# MCU_Module_V3.net
KiCad netlist of a schematic drawn in EAGLE
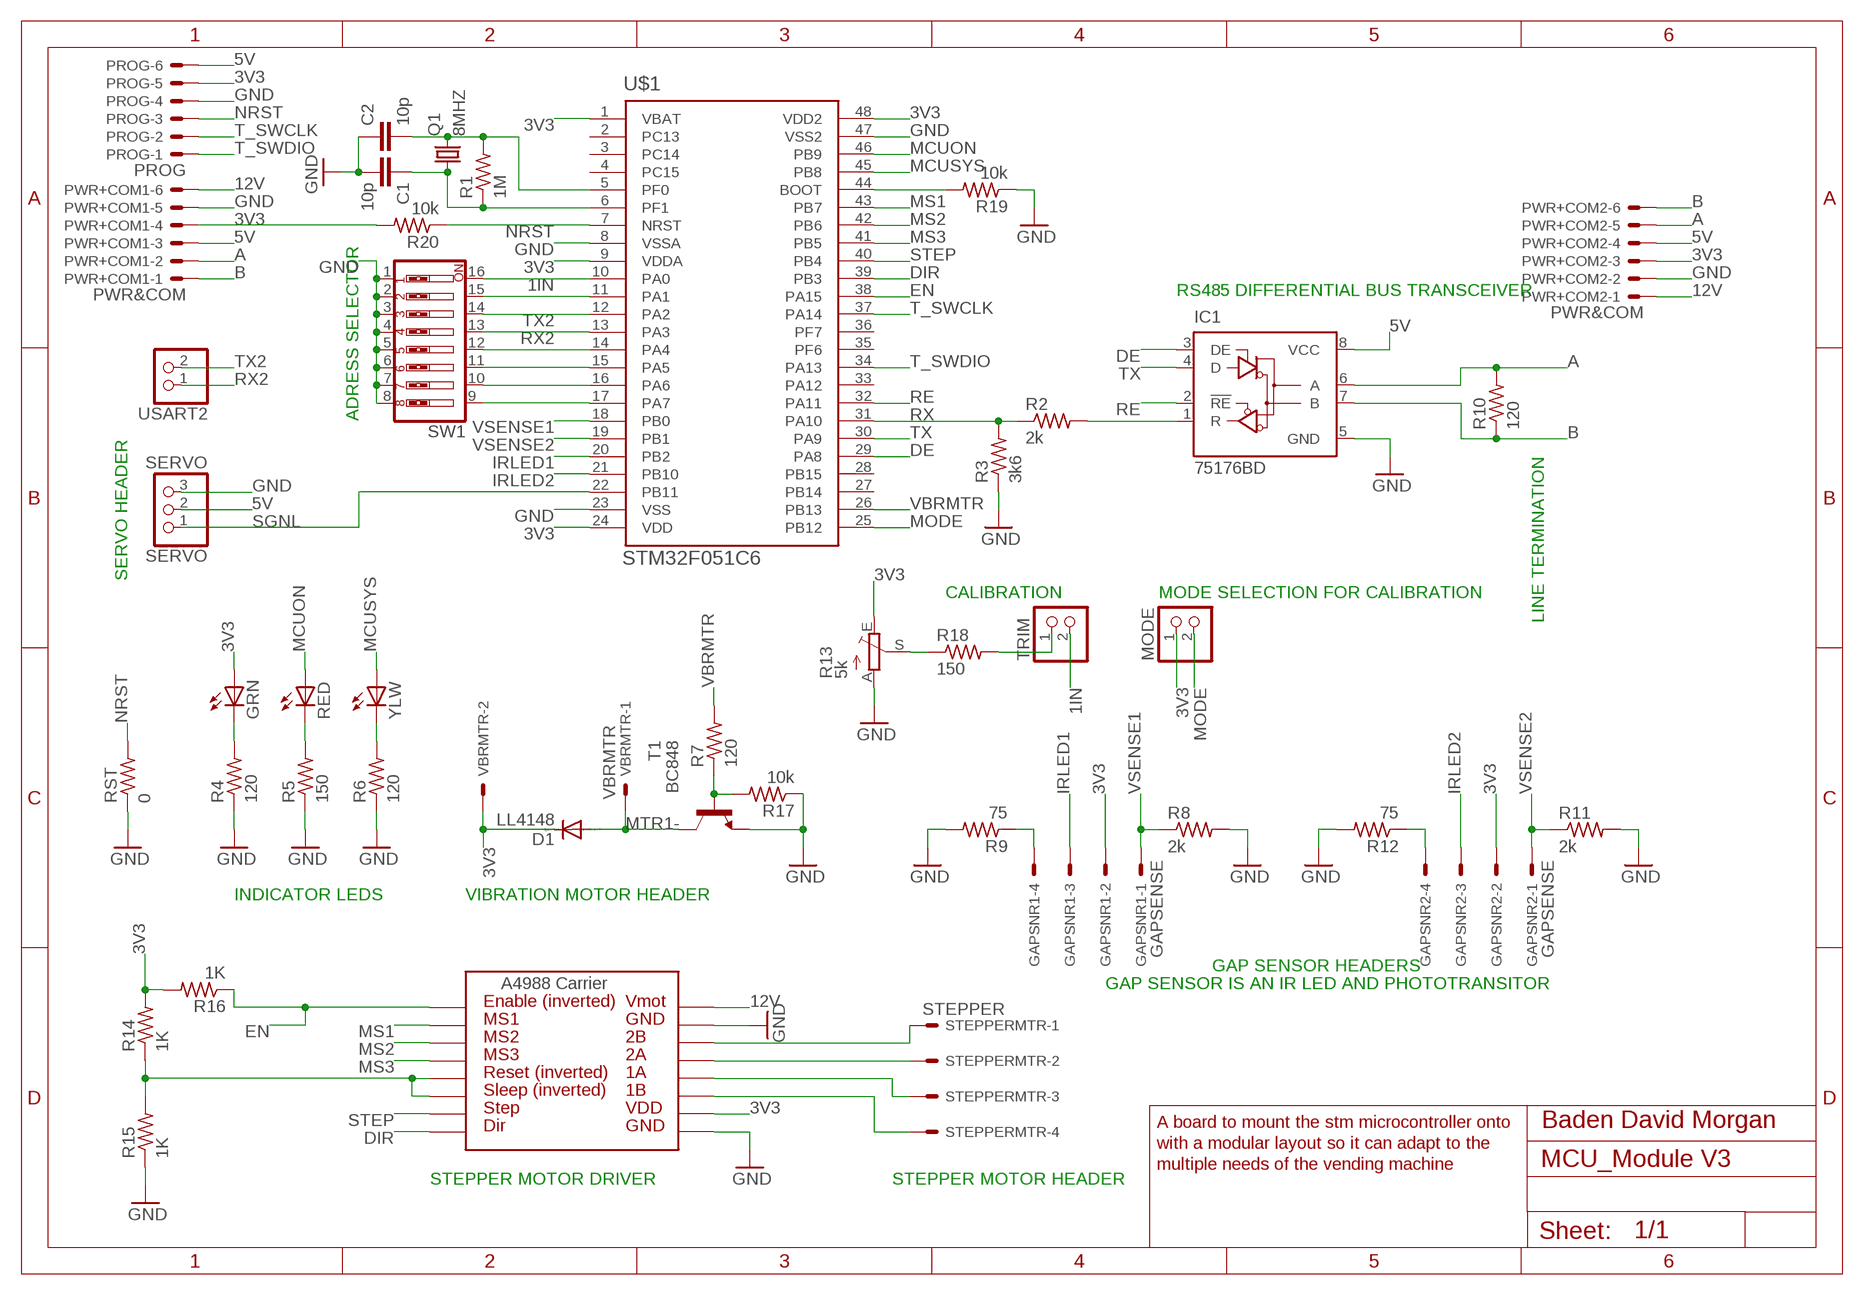
[diagram p0: schematic, sheet 1]

(export (version "E")
  (design (tool "Eeschema 10.0.6"))
  (components
    (comp (ref "C1")
      (value "10p")
      (footprint "eagle-import:C0805")
      (libsource (lib "eagle-import") (part "C-EUC0805"))
    )
    (comp (ref "C2")
      (value "10p")
      (footprint "eagle-import:C0805")
      (libsource (lib "eagle-import") (part "C-EUC0805"))
    )
    (comp (ref "D1")
      (value "LL4148")
      (footprint "eagle-import:SOD80C")
      (libsource (lib "eagle-import") (part "PMLL4150"))
    )
    (comp (ref "GAPSNR1")
      (value "GAPSENSE")
      (footprint "eagle-import:6410-04")
      (libsource (lib "eagle-import") (part "22-?-0427-2041"))
    )
    (comp (ref "GAPSNR2")
      (value "GAPSENSE")
      (footprint "eagle-import:6410-04")
      (libsource (lib "eagle-import") (part "22-?-0427-2041"))
    )
    (comp (ref "GRN")
      (value "LEDSML1206")
      (footprint "eagle-import:SML1206")
      (libsource (lib "eagle-import") (part "LEDSML1206"))
    )
    (comp (ref "IC1")
      (value "75176BD")
      (footprint "eagle-import:D_R-PDSO-G8")
      (libsource (lib "eagle-import") (part "75176AD"))
    )
    (comp (ref "MODE")
      (value "PINHD-1X2")
      (footprint "eagle-import:1X02")
      (libsource (lib "eagle-import") (part "PINHD-1X2"))
    )
    (comp (ref "PROG")
      (value "PROG")
      (footprint "eagle-import:6410-06")
      (libsource (lib "eagle-import") (part "22-?-0627-2061"))
    )
    (comp (ref "PWR+COM1")
      (value "PWR&COM")
      (footprint "eagle-import:7395-06")
      (libsource (lib "eagle-import") (part "22-?-0605-7068"))
    )
    (comp (ref "PWR+COM2")
      (value "PWR&COM")
      (footprint "eagle-import:7395-06")
      (libsource (lib "eagle-import") (part "22-?-0605-7068"))
    )
    (comp (ref "Q1")
      (value "8MHZ")
      (footprint "eagle-import:SM49")
      (libsource (lib "eagle-import") (part "CRYSTALSM49"))
    )
    (comp (ref "R1")
      (value "1M")
      (footprint "eagle-import:R0805")
      (libsource (lib "eagle-import") (part "R-US_R0805"))
    )
    (comp (ref "R2")
      (value "2k")
      (footprint "eagle-import:R0805")
      (libsource (lib "eagle-import") (part "resistor_R-US_R0805"))
    )
    (comp (ref "R3")
      (value "3k6")
      (footprint "eagle-import:R0805")
      (libsource (lib "eagle-import") (part "resistor_R-US_R0805"))
    )
    (comp (ref "R4")
      (value "120")
      (footprint "eagle-import:R0805")
      (libsource (lib "eagle-import") (part "R-US_R0805"))
    )
    (comp (ref "R5")
      (value "150")
      (footprint "eagle-import:R0805")
      (libsource (lib "eagle-import") (part "R-US_R0805"))
    )
    (comp (ref "R6")
      (value "120")
      (footprint "eagle-import:R0805")
      (libsource (lib "eagle-import") (part "R-US_R0805"))
    )
    (comp (ref "R7")
      (value "120")
      (footprint "eagle-import:R0805")
      (libsource (lib "eagle-import") (part "R-US_R0805"))
    )
    (comp (ref "R8")
      (value "2k")
      (footprint "eagle-import:R0805")
      (libsource (lib "eagle-import") (part "resistor_R-US_R0805"))
    )
    (comp (ref "R9")
      (value "75")
      (footprint "eagle-import:R0805")
      (libsource (lib "eagle-import") (part "R-US_R0805"))
    )
    (comp (ref "R10")
      (value "120")
      (footprint "eagle-import:R0805")
      (libsource (lib "eagle-import") (part "resistor_R-US_R0805"))
    )
    (comp (ref "R11")
      (value "2k")
      (footprint "eagle-import:R0805")
      (libsource (lib "eagle-import") (part "resistor_R-US_R0805"))
    )
    (comp (ref "R12")
      (value "75")
      (footprint "eagle-import:R0805")
      (libsource (lib "eagle-import") (part "R-US_R0805"))
    )
    (comp (ref "R13")
      (value "5k")
      (footprint "eagle-import:B25P")
      (libsource (lib "eagle-import") (part "TRIM_EU-B25P"))
    )
    (comp (ref "R14")
      (value "1K")
      (footprint "eagle-import:R0805")
      (libsource (lib "eagle-import") (part "R-US_R0805"))
    )
    (comp (ref "R15")
      (value "1K")
      (footprint "eagle-import:R0805")
      (libsource (lib "eagle-import") (part "R-US_R0805"))
    )
    (comp (ref "R16")
      (value "1K")
      (footprint "eagle-import:R0805")
      (libsource (lib "eagle-import") (part "R-US_R0805"))
    )
    (comp (ref "R17")
      (value "10k")
      (footprint "eagle-import:R0805")
      (libsource (lib "eagle-import") (part "R-US_R0805"))
    )
    (comp (ref "R18")
      (value "150")
      (footprint "eagle-import:R0805")
      (libsource (lib "eagle-import") (part "resistor_R-US_R0805"))
    )
    (comp (ref "R19")
      (value "10k")
      (footprint "eagle-import:R0805")
      (libsource (lib "eagle-import") (part "R-US_R0805"))
    )
    (comp (ref "R20")
      (value "10k")
      (footprint "eagle-import:R0805")
      (libsource (lib "eagle-import") (part "R-US_R0805"))
    )
    (comp (ref "RED")
      (value "LEDSML1206")
      (footprint "eagle-import:SML1206")
      (libsource (lib "eagle-import") (part "LEDSML1206"))
    )
    (comp (ref "RST")
      (value "0")
      (footprint "eagle-import:R0805")
      (libsource (lib "eagle-import") (part "R-US_R0805"))
    )
    (comp (ref "SERVO")
      (value "SERVO")
      (footprint "eagle-import:1X03")
      (libsource (lib "eagle-import") (part "PINHD-1X3"))
    )
    (comp (ref "STEPPERMTR")
      (value "STEPPER")
      (footprint "eagle-import:6410-04")
      (libsource (lib "eagle-import") (part "22-?-0427-2041"))
    )
    (comp (ref "SW1")
      (value "SW_DIP-8")
      (footprint "eagle-import:EDG-08")
      (libsource (lib "eagle-import") (part "SW_DIP-8"))
    )
    (comp (ref "T1")
      (value "BC848")
      (footprint "eagle-import:SOT23")
      (libsource (lib "eagle-import") (part "BC848"))
    )
    (comp (ref "TRIM")
      (value "PINHD-1X2")
      (footprint "eagle-import:1X02")
      (libsource (lib "eagle-import") (part "PINHD-1X2"))
    )
    (comp (ref "U$1")
      (value "STM32F051C6")
      (footprint "eagle-import:QFP50P900X900X160-48N")
      (libsource (lib "eagle-import") (part "STM32F051C6"))
    )
    (comp (ref "U$2")
      (value "A4983CARRIER")
      (footprint "eagle-import:A4988BREAKOUT")
      (libsource (lib "eagle-import") (part "A4983CARRIER"))
    )
    (comp (ref "USART2")
      (value "PINHD-1X2")
      (footprint "eagle-import:1X02")
      (libsource (lib "eagle-import") (part "PINHD-1X2"))
    )
    (comp (ref "VBRMTR")
      (value "VBRMTR")
      (footprint "eagle-import:6410-02")
      (libsource (lib "eagle-import") (part "22-?-0227-2021"))
    )
    (comp (ref "YLW")
      (value "LEDSML1206")
      (footprint "eagle-import:SML1206")
      (libsource (lib "eagle-import") (part "LEDSML1206"))
    )
  )
  (nets
    (net (code "1") (name "/1IN") (class "Default")
      (node (ref "SW1") (pin "16") (pinfunction "16_16") (pintype "passive"))
      (node (ref "TRIM") (pin "2") (pinfunction "2_2") (pintype "passive"))
      (node (ref "U$1") (pin "10") (pinfunction "PA0_10") (pintype "bidirectional"))
    )
    (net (code "2") (name "/3V3") (class "Default")
      (node (ref "D1") (pin "C") (pinfunction "C_C") (pintype "passive"))
      (node (ref "GAPSNR1") (pin "2") (pinfunction "S_2") (pintype "passive"))
      (node (ref "GAPSNR2") (pin "2") (pinfunction "S_2") (pintype "passive"))
      (node (ref "GRN") (pin "A") (pinfunction "A_A") (pintype "passive"))
      (node (ref "MODE") (pin "1") (pinfunction "1_1") (pintype "passive"))
      (node (ref "PROG") (pin "5") (pinfunction "S_5") (pintype "passive"))
      (node (ref "PWR+COM1") (pin "4") (pinfunction "S_4") (pintype "passive"))
      (node (ref "PWR+COM2") (pin "3") (pinfunction "S_3") (pintype "passive"))
      (node (ref "R13") (pin "E") (pinfunction "E_E") (pintype "passive"))
      (node (ref "R14") (pin "2") (pinfunction "2_2") (pintype "passive"))
      (node (ref "R16") (pin "2") (pinfunction "2_2") (pintype "passive"))
      (node (ref "R20") (pin "2") (pinfunction "2_2") (pintype "passive"))
      (node (ref "U$1") (pin "1") (pinfunction "VBAT_1") (pintype "bidirectional"))
      (node (ref "U$1") (pin "24") (pinfunction "VDD_24") (pintype "bidirectional"))
      (node (ref "U$1") (pin "48") (pinfunction "VDD2_48") (pintype "bidirectional"))
      (node (ref "U$1") (pin "9") (pinfunction "VDDA_9") (pintype "bidirectional"))
      (node (ref "U$2") (pin "VDD") (pinfunction "VDD_VDD") (pintype "power_in"))
      (node (ref "VBRMTR") (pin "2") (pinfunction "S_2") (pintype "passive"))
    )
    (net (code "3") (name "/5V") (class "Default")
      (node (ref "IC1") (pin "8") (pinfunction "VCC_8") (pintype "power_in"))
      (node (ref "PROG") (pin "6") (pinfunction "S_6") (pintype "passive"))
      (node (ref "PWR+COM1") (pin "3") (pinfunction "S_3") (pintype "passive"))
      (node (ref "PWR+COM2") (pin "4") (pinfunction "S_4") (pintype "passive"))
      (node (ref "SERVO") (pin "2") (pinfunction "2_2") (pintype "passive"))
    )
    (net (code "4") (name "/12V") (class "Default")
      (node (ref "PWR+COM1") (pin "6") (pinfunction "S_6") (pintype "passive"))
      (node (ref "PWR+COM2") (pin "1") (pinfunction "S_1") (pintype "passive"))
      (node (ref "U$2") (pin "VMOT") (pinfunction "VMOT_VMOT") (pintype "power_in"))
    )
    (net (code "5") (name "/A") (class "Default")
      (node (ref "IC1") (pin "6") (pinfunction "A_6") (pintype "output"))
      (node (ref "PWR+COM1") (pin "2") (pinfunction "S_2") (pintype "passive"))
      (node (ref "PWR+COM2") (pin "5") (pinfunction "S_5") (pintype "passive"))
      (node (ref "R10") (pin "2") (pinfunction "2_2") (pintype "passive"))
    )
    (net (code "6") (name "/B") (class "Default")
      (node (ref "IC1") (pin "7") (pinfunction "B_7") (pintype "output"))
      (node (ref "PWR+COM1") (pin "1") (pinfunction "S_1") (pintype "passive"))
      (node (ref "PWR+COM2") (pin "6") (pinfunction "S_6") (pintype "passive"))
      (node (ref "R10") (pin "1") (pinfunction "1_1") (pintype "passive"))
    )
    (net (code "7") (name "/DE") (class "Default")
      (node (ref "IC1") (pin "3") (pinfunction "DE_3") (pintype "input"))
      (node (ref "U$1") (pin "29") (pinfunction "PA8_29") (pintype "bidirectional"))
    )
    (net (code "8") (name "/DIR") (class "Default")
      (node (ref "U$1") (pin "39") (pinfunction "PB3_39") (pintype "bidirectional"))
      (node (ref "U$2") (pin "DIR") (pinfunction "DIR_DIR") (pintype "input"))
    )
    (net (code "9") (name "/EN") (class "Default")
      (node (ref "R16") (pin "1") (pinfunction "1_1") (pintype "passive"))
      (node (ref "U$1") (pin "38") (pinfunction "PA15_38") (pintype "bidirectional"))
      (node (ref "U$2") (pin "EN") (pinfunction "EN_EN") (pintype "input"))
    )
    (net (code "10") (name "/IRLED1") (class "Default")
      (node (ref "GAPSNR1") (pin "3") (pinfunction "S_3") (pintype "passive"))
      (node (ref "U$1") (pin "20") (pinfunction "PB2_20") (pintype "bidirectional"))
    )
    (net (code "11") (name "/IRLED2") (class "Default")
      (node (ref "GAPSNR2") (pin "3") (pinfunction "S_3") (pintype "passive"))
      (node (ref "U$1") (pin "21") (pinfunction "PB10_21") (pintype "bidirectional"))
    )
    (net (code "12") (name "/MCUON") (class "Default")
      (node (ref "RED") (pin "A") (pinfunction "A_A") (pintype "passive"))
      (node (ref "U$1") (pin "46") (pinfunction "PB9_46") (pintype "bidirectional"))
    )
    (net (code "13") (name "/MCUSYS") (class "Default")
      (node (ref "U$1") (pin "45") (pinfunction "PB8_45") (pintype "bidirectional"))
      (node (ref "YLW") (pin "A") (pinfunction "A_A") (pintype "passive"))
    )
    (net (code "14") (name "/MODE") (class "Default")
      (node (ref "MODE") (pin "2") (pinfunction "2_2") (pintype "passive"))
      (node (ref "U$1") (pin "25") (pinfunction "PB12_25") (pintype "bidirectional"))
    )
    (net (code "15") (name "/MS1") (class "Default")
      (node (ref "U$1") (pin "43") (pinfunction "PB7_43") (pintype "bidirectional"))
      (node (ref "U$2") (pin "MS1") (pinfunction "MS1_MS1") (pintype "input"))
    )
    (net (code "16") (name "/MS2") (class "Default")
      (node (ref "U$1") (pin "42") (pinfunction "PB6_42") (pintype "bidirectional"))
      (node (ref "U$2") (pin "MS2") (pinfunction "MS2_MS2") (pintype "input"))
    )
    (net (code "17") (name "/MS3") (class "Default")
      (node (ref "U$1") (pin "41") (pinfunction "PB5_41") (pintype "bidirectional"))
      (node (ref "U$2") (pin "MS3") (pinfunction "MS3_MS3") (pintype "input"))
    )
    (net (code "18") (name "/MTR1-") (class "Default")
      (node (ref "D1") (pin "A") (pinfunction "A_A") (pintype "passive"))
      (node (ref "T1") (pin "3") (pinfunction "C_3") (pintype "passive"))
      (node (ref "VBRMTR") (pin "1") (pinfunction "S_1") (pintype "passive"))
    )
    (net (code "19") (name "/NRST") (class "Default")
      (node (ref "PROG") (pin "3") (pinfunction "S_3") (pintype "passive"))
      (node (ref "R20") (pin "1") (pinfunction "1_1") (pintype "passive"))
      (node (ref "RST") (pin "2") (pinfunction "2_2") (pintype "passive"))
      (node (ref "U$1") (pin "7") (pinfunction "NRST_7") (pintype "bidirectional"))
    )
    (net (code "20") (name "/RE") (class "Default")
      (node (ref "IC1") (pin "2") (pinfunction "~{RE}_2") (pintype "input"))
      (node (ref "U$1") (pin "32") (pinfunction "PA11_32") (pintype "bidirectional"))
    )
    (net (code "21") (name "/RX") (class "Default")
      (node (ref "R2") (pin "1") (pinfunction "1_1") (pintype "passive"))
      (node (ref "R3") (pin "2") (pinfunction "2_2") (pintype "passive"))
      (node (ref "U$1") (pin "31") (pinfunction "PA10_31") (pintype "bidirectional"))
    )
    (net (code "22") (name "/RX2") (class "Default")
      (node (ref "SW1") (pin "13") (pinfunction "13_13") (pintype "passive"))
      (node (ref "U$1") (pin "13") (pinfunction "PA3_13") (pintype "bidirectional"))
      (node (ref "USART2") (pin "1") (pinfunction "1_1") (pintype "passive"))
    )
    (net (code "23") (name "/SGNL") (class "Default")
      (node (ref "SERVO") (pin "1") (pinfunction "1_1") (pintype "passive"))
      (node (ref "U$1") (pin "22") (pinfunction "PB11_22") (pintype "bidirectional"))
    )
    (net (code "24") (name "/STEP") (class "Default")
      (node (ref "U$1") (pin "40") (pinfunction "PB4_40") (pintype "bidirectional"))
      (node (ref "U$2") (pin "STEP") (pinfunction "STEP_STEP") (pintype "input"))
    )
    (net (code "25") (name "/TX") (class "Default")
      (node (ref "IC1") (pin "4") (pinfunction "D_4") (pintype "input"))
      (node (ref "U$1") (pin "30") (pinfunction "PA9_30") (pintype "bidirectional"))
    )
    (net (code "26") (name "/TX2") (class "Default")
      (node (ref "SW1") (pin "14") (pinfunction "14_14") (pintype "passive"))
      (node (ref "U$1") (pin "12") (pinfunction "PA2_12") (pintype "bidirectional"))
      (node (ref "USART2") (pin "2") (pinfunction "2_2") (pintype "passive"))
    )
    (net (code "27") (name "/T_SWCLK") (class "Default")
      (node (ref "PROG") (pin "2") (pinfunction "S_2") (pintype "passive"))
      (node (ref "U$1") (pin "37") (pinfunction "PA14_37") (pintype "bidirectional"))
    )
    (net (code "28") (name "/T_SWDIO") (class "Default")
      (node (ref "PROG") (pin "1") (pinfunction "S_1") (pintype "passive"))
      (node (ref "U$1") (pin "34") (pinfunction "PA13_34") (pintype "bidirectional"))
    )
    (net (code "29") (name "/VBRMTR") (class "Default")
      (node (ref "R7") (pin "2") (pinfunction "2_2") (pintype "passive"))
      (node (ref "U$1") (pin "26") (pinfunction "PB13_26") (pintype "bidirectional"))
    )
    (net (code "30") (name "/VSENSE1") (class "Default")
      (node (ref "GAPSNR1") (pin "1") (pinfunction "S_1") (pintype "passive"))
      (node (ref "R8") (pin "1") (pinfunction "1_1") (pintype "passive"))
      (node (ref "U$1") (pin "18") (pinfunction "PB0_18") (pintype "bidirectional"))
    )
    (net (code "31") (name "/VSENSE2") (class "Default")
      (node (ref "GAPSNR2") (pin "1") (pinfunction "S_1") (pintype "passive"))
      (node (ref "R11") (pin "1") (pinfunction "1_1") (pintype "passive"))
      (node (ref "U$1") (pin "19") (pinfunction "PB1_19") (pintype "bidirectional"))
    )
    (net (code "32") (name "GND") (class "Default")
      (node (ref "C1") (pin "2") (pinfunction "2_2") (pintype "passive"))
      (node (ref "C2") (pin "1") (pinfunction "1_1") (pintype "passive"))
      (node (ref "IC1") (pin "5") (pinfunction "GND_5") (pintype "power_in"))
      (node (ref "PROG") (pin "4") (pinfunction "S_4") (pintype "passive"))
      (node (ref "PWR+COM1") (pin "5") (pinfunction "S_5") (pintype "passive"))
      (node (ref "PWR+COM2") (pin "2") (pinfunction "S_2") (pintype "passive"))
      (node (ref "R11") (pin "2") (pinfunction "2_2") (pintype "passive"))
      (node (ref "R12") (pin "2") (pinfunction "2_2") (pintype "passive"))
      (node (ref "R13") (pin "A") (pinfunction "A_A") (pintype "passive"))
      (node (ref "R15") (pin "1") (pinfunction "1_1") (pintype "passive"))
      (node (ref "R17") (pin "1") (pinfunction "1_1") (pintype "passive"))
      (node (ref "R19") (pin "1") (pinfunction "1_1") (pintype "passive"))
      (node (ref "R3") (pin "1") (pinfunction "1_1") (pintype "passive"))
      (node (ref "R4") (pin "1") (pinfunction "1_1") (pintype "passive"))
      (node (ref "R5") (pin "1") (pinfunction "1_1") (pintype "passive"))
      (node (ref "R6") (pin "1") (pinfunction "1_1") (pintype "passive"))
      (node (ref "R8") (pin "2") (pinfunction "2_2") (pintype "passive"))
      (node (ref "R9") (pin "2") (pinfunction "2_2") (pintype "passive"))
      (node (ref "RST") (pin "1") (pinfunction "1_1") (pintype "passive"))
      (node (ref "SERVO") (pin "3") (pinfunction "3_3") (pintype "passive"))
      (node (ref "SW1") (pin "1") (pinfunction "1_1") (pintype "passive"))
      (node (ref "SW1") (pin "2") (pinfunction "2_2") (pintype "passive"))
      (node (ref "SW1") (pin "3") (pinfunction "3_3") (pintype "passive"))
      (node (ref "SW1") (pin "4") (pinfunction "4_4") (pintype "passive"))
      (node (ref "SW1") (pin "5") (pinfunction "5_5") (pintype "passive"))
      (node (ref "SW1") (pin "6") (pinfunction "6_6") (pintype "passive"))
      (node (ref "SW1") (pin "7") (pinfunction "7_7") (pintype "passive"))
      (node (ref "SW1") (pin "8") (pinfunction "8_8") (pintype "passive"))
      (node (ref "T1") (pin "2") (pinfunction "E_2") (pintype "passive"))
      (node (ref "U$1") (pin "23") (pinfunction "VSS_23") (pintype "bidirectional"))
      (node (ref "U$1") (pin "47") (pinfunction "VSS2_47") (pintype "bidirectional"))
      (node (ref "U$1") (pin "8") (pinfunction "VSSA_8") (pintype "bidirectional"))
      (node (ref "U$2") (pin "GND") (pinfunction "GND_GND") (pintype "power_in"))
      (node (ref "U$2") (pin "GND@0") (pinfunction "GND_GND@0") (pintype "power_in"))
    )
    (net (code "33") (name "Net-(GAPSNR1D-S)") (class "Default")
      (node (ref "GAPSNR1") (pin "4") (pinfunction "S_4") (pintype "passive"))
      (node (ref "R9") (pin "1") (pinfunction "1_1") (pintype "passive"))
    )
    (net (code "34") (name "Net-(GAPSNR2D-S)") (class "Default")
      (node (ref "GAPSNR2") (pin "4") (pinfunction "S_4") (pintype "passive"))
      (node (ref "R12") (pin "1") (pinfunction "1_1") (pintype "passive"))
    )
    (net (code "35") (name "Net-(GRN-PadC)") (class "Default")
      (node (ref "GRN") (pin "C") (pinfunction "C_C") (pintype "passive"))
      (node (ref "R4") (pin "2") (pinfunction "2_2") (pintype "passive"))
    )
    (net (code "36") (name "Net-(IC1-R)") (class "Default")
      (node (ref "IC1") (pin "1") (pinfunction "R_1") (pintype "input"))
      (node (ref "R2") (pin "2") (pinfunction "2_2") (pintype "passive"))
    )
    (net (code "37") (name "Net-(R5-Pad2)") (class "Default")
      (node (ref "R5") (pin "2") (pinfunction "2_2") (pintype "passive"))
      (node (ref "RED") (pin "C") (pinfunction "C_C") (pintype "passive"))
    )
    (net (code "38") (name "Net-(R6-Pad2)") (class "Default")
      (node (ref "R6") (pin "2") (pinfunction "2_2") (pintype "passive"))
      (node (ref "YLW") (pin "C") (pinfunction "C_C") (pintype "passive"))
    )
    (net (code "39") (name "Net-(R13-PadS)") (class "Default")
      (node (ref "R13") (pin "S") (pinfunction "S_S") (pintype "passive"))
      (node (ref "R18") (pin "1") (pinfunction "1_1") (pintype "passive"))
    )
    (net (code "40") (name "Net-(R18-Pad2)") (class "Default")
      (node (ref "R18") (pin "2") (pinfunction "2_2") (pintype "passive"))
      (node (ref "TRIM") (pin "1") (pinfunction "1_1") (pintype "passive"))
    )
    (net (code "41") (name "Net-(STEPPERMTRA-S)") (class "Default")
      (node (ref "STEPPERMTR") (pin "1") (pinfunction "S_1") (pintype "passive"))
      (node (ref "U$2") (pin "2B") (pinfunction "2B_2B") (pintype "output"))
    )
    (net (code "42") (name "Net-(STEPPERMTRB-S)") (class "Default")
      (node (ref "STEPPERMTR") (pin "2") (pinfunction "S_2") (pintype "passive"))
      (node (ref "U$2") (pin "2A") (pinfunction "2A_2A") (pintype "output"))
    )
    (net (code "43") (name "Net-(STEPPERMTRC-S)") (class "Default")
      (node (ref "STEPPERMTR") (pin "3") (pinfunction "S_3") (pintype "passive"))
      (node (ref "U$2") (pin "1A") (pinfunction "1A_1A") (pintype "output"))
    )
    (net (code "44") (name "Net-(STEPPERMTRD-S)") (class "Default")
      (node (ref "STEPPERMTR") (pin "4") (pinfunction "S_4") (pintype "passive"))
      (node (ref "U$2") (pin "1B") (pinfunction "1B_1B") (pintype "output"))
    )
    (net (code "45") (name "Net-(T1-B)") (class "Default")
      (node (ref "R17") (pin "2") (pinfunction "2_2") (pintype "passive"))
      (node (ref "R7") (pin "1") (pinfunction "1_1") (pintype "passive"))
      (node (ref "T1") (pin "1") (pinfunction "B_1") (pintype "passive"))
    )
    (net (code "46") (name "Net-(U$1-BOOT)") (class "Default")
      (node (ref "R19") (pin "2") (pinfunction "2_2") (pintype "passive"))
      (node (ref "U$1") (pin "44") (pinfunction "BOOT_44") (pintype "bidirectional"))
    )
    (net (code "47") (name "Net-(U$1-PA1)") (class "Default")
      (node (ref "SW1") (pin "15") (pinfunction "15_15") (pintype "passive"))
      (node (ref "U$1") (pin "11") (pinfunction "PA1_11") (pintype "bidirectional"))
    )
    (net (code "48") (name "Net-(U$1-PA4)") (class "Default")
      (node (ref "SW1") (pin "12") (pinfunction "12_12") (pintype "passive"))
      (node (ref "U$1") (pin "14") (pinfunction "PA4_14") (pintype "bidirectional"))
    )
    (net (code "49") (name "Net-(U$1-PA5)") (class "Default")
      (node (ref "SW1") (pin "11") (pinfunction "11_11") (pintype "passive"))
      (node (ref "U$1") (pin "15") (pinfunction "PA5_15") (pintype "bidirectional"))
    )
    (net (code "50") (name "Net-(U$1-PA6)") (class "Default")
      (node (ref "SW1") (pin "10") (pinfunction "10_10") (pintype "passive"))
      (node (ref "U$1") (pin "16") (pinfunction "PA6_16") (pintype "bidirectional"))
    )
    (net (code "51") (name "Net-(U$1-PA7)") (class "Default")
      (node (ref "SW1") (pin "9") (pinfunction "9_9") (pintype "passive"))
      (node (ref "U$1") (pin "17") (pinfunction "PA7_17") (pintype "bidirectional"))
    )
    (net (code "52") (name "Net-(U$1-PF0)") (class "Default")
      (node (ref "C2") (pin "2") (pinfunction "2_2") (pintype "passive"))
      (node (ref "Q1") (pin "2") (pinfunction "2_2") (pintype "passive"))
      (node (ref "R1") (pin "2") (pinfunction "2_2") (pintype "passive"))
      (node (ref "U$1") (pin "5") (pinfunction "PF0_5") (pintype "bidirectional"))
    )
    (net (code "53") (name "Net-(U$1-PF1)") (class "Default")
      (node (ref "C1") (pin "1") (pinfunction "1_1") (pintype "passive"))
      (node (ref "Q1") (pin "1") (pinfunction "1_1") (pintype "passive"))
      (node (ref "R1") (pin "1") (pinfunction "1_1") (pintype "passive"))
      (node (ref "U$1") (pin "6") (pinfunction "PF1_6") (pintype "bidirectional"))
    )
    (net (code "54") (name "Net-(U$2-SLEEP)") (class "Default")
      (node (ref "R14") (pin "1") (pinfunction "1_1") (pintype "passive"))
      (node (ref "R15") (pin "2") (pinfunction "2_2") (pintype "passive"))
      (node (ref "U$2") (pin "RST") (pinfunction "RST_RST") (pintype "input"))
      (node (ref "U$2") (pin "SLP") (pinfunction "SLEEP_SLP") (pintype "input"))
    )
    (net (code "55") (name "unconnected-(U$1-PA12-Pad33)") (class "Default")
      (node (ref "U$1") (pin "33") (pinfunction "PA12_33") (pintype "bidirectional"))
    )
    (net (code "56") (name "unconnected-(U$1-PB14-Pad27)") (class "Default")
      (node (ref "U$1") (pin "27") (pinfunction "PB14_27") (pintype "bidirectional"))
    )
    (net (code "57") (name "unconnected-(U$1-PB15-Pad28)") (class "Default")
      (node (ref "U$1") (pin "28") (pinfunction "PB15_28") (pintype "bidirectional"))
    )
    (net (code "58") (name "unconnected-(U$1-PC13-Pad2)") (class "Default")
      (node (ref "U$1") (pin "2") (pinfunction "PC13_2") (pintype "bidirectional"))
    )
    (net (code "59") (name "unconnected-(U$1-PC14-Pad3)") (class "Default")
      (node (ref "U$1") (pin "3") (pinfunction "PC14_3") (pintype "bidirectional"))
    )
    (net (code "60") (name "unconnected-(U$1-PC15-Pad4)") (class "Default")
      (node (ref "U$1") (pin "4") (pinfunction "PC15_4") (pintype "bidirectional"))
    )
    (net (code "61") (name "unconnected-(U$1-PF6-Pad35)") (class "Default")
      (node (ref "U$1") (pin "35") (pinfunction "PF6_35") (pintype "bidirectional"))
    )
    (net (code "62") (name "unconnected-(U$1-PF7-Pad36)") (class "Default")
      (node (ref "U$1") (pin "36") (pinfunction "PF7_36") (pintype "bidirectional"))
    )
  )
)
